# Voltage_measure.net
KiCad netlist of a schematic drawn in Altium Designer
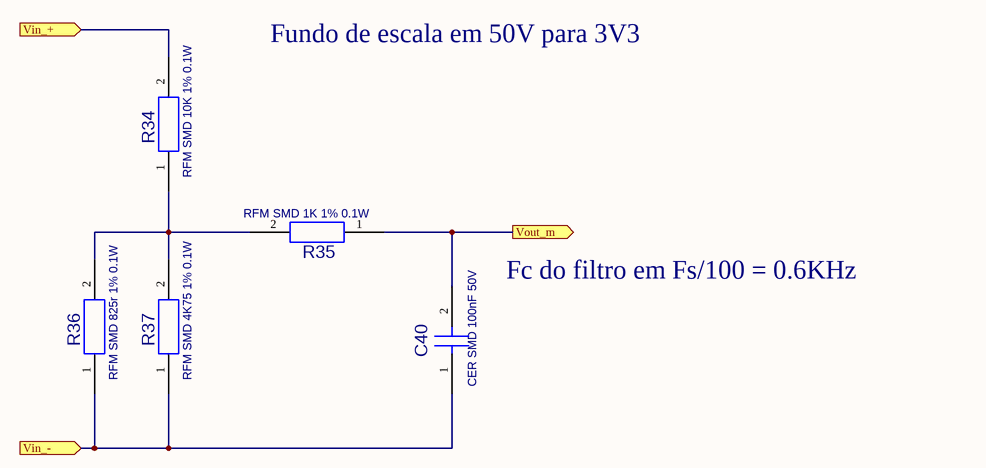
[diagram p0: Voltage_measure.SchDoc]

(export (version "E")
  (design (tool "Eeschema 10.0.6"))
  (components
    (comp (ref "C40")
      (value "CER SMD 100nF 50V")
      (footprint "C0805_R_V0")
      (fields (field (name "Comment") "10192075"))
      (libsource (lib "Buck_Converter") (part "10192075"))
    )
    (comp (ref "R34")
      (value "RFM SMD 10K 1% 0.1W")
      (footprint "R0805_R_V0")
      (fields (field (name "Comment") "10118076"))
      (libsource (lib "Buck_Converter") (part "10118077"))
    )
    (comp (ref "R35")
      (value "RFM SMD 1K 1% 0.1W")
      (footprint "R0805_R_V0")
      (fields (field (name "Comment") "10118077"))
      (libsource (lib "Buck_Converter") (part "10118077"))
    )
    (comp (ref "R36")
      (value "RFM SMD 825r 1% 0.1W")
      (footprint "R0805_R_V0")
      (fields (field (name "Comment") "10191983"))
      (libsource (lib "Buck_Converter") (part "10118077"))
    )
    (comp (ref "R37")
      (value "RFM SMD 4K75 1% 0.1W")
      (footprint "R0805_R_V0")
      (fields (field (name "Comment") "10191972"))
      (libsource (lib "Buck_Converter") (part "10118077"))
    )
  )
  (nets
    (net (code "1") (name "/Vin_+") (class "Default")
      (node (ref "R34") (pin "2") (pinfunction "2_2") (pintype "passive"))
    )
    (net (code "2") (name "/Vin_-") (class "Default")
      (node (ref "C40") (pin "1") (pinfunction "1_1") (pintype "passive"))
      (node (ref "R36") (pin "1") (pinfunction "1_1") (pintype "passive"))
      (node (ref "R37") (pin "1") (pinfunction "1_1") (pintype "passive"))
    )
    (net (code "3") (name "/Vout_m") (class "Default")
      (node (ref "C40") (pin "2") (pinfunction "2_2") (pintype "passive"))
      (node (ref "R35") (pin "1") (pinfunction "1_1") (pintype "passive"))
    )
    (net (code "4") (name "Net-(R34-Pad1)") (class "Default")
      (node (ref "R34") (pin "1") (pinfunction "1_1") (pintype "passive"))
      (node (ref "R35") (pin "2") (pinfunction "2_2") (pintype "passive"))
      (node (ref "R36") (pin "2") (pinfunction "2_2") (pintype "passive"))
      (node (ref "R37") (pin "2") (pinfunction "2_2") (pintype "passive"))
    )
  )
)
